# LED_board_2.net
KiCad netlist of a schematic drawn in EAGLE
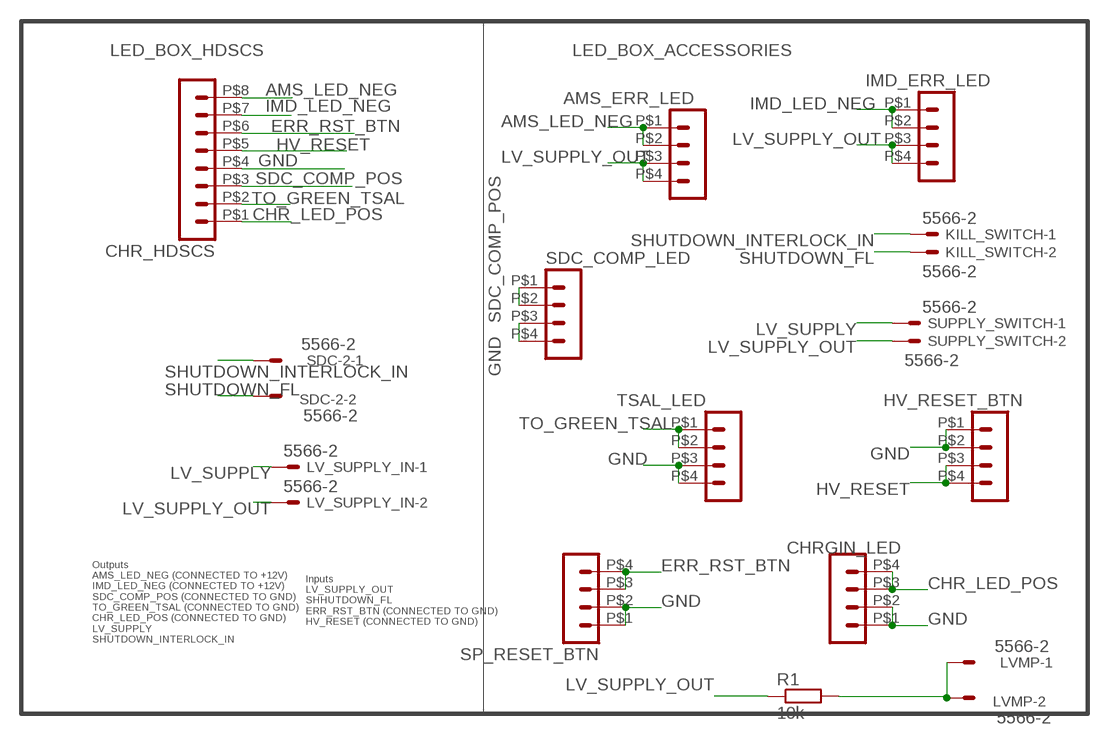
[diagram p0: schematic, sheet 1]

(export (version "E")
  (design (tool "Eeschema 10.0.6"))
  (components
    (comp (ref "AMS_ERR_LED")
      (value "HEADER_POS4_43045-0412")
      (footprint "eagle-import:43045-0412")
      (libsource (lib "eagle-import") (part "IIT_BOMBAY_Racing2 (1)_HEADER_POS4_?43045-0412"))
    )
    (comp (ref "CHRGIN_LED")
      (value "HEADER_POS4_43045-0412")
      (footprint "eagle-import:43045-0412")
      (libsource (lib "eagle-import") (part "IIT_BOMBAY_Racing2 (1)_HEADER_POS4_?43045-0412"))
    )
    (comp (ref "CHR_HDSCS")
      (value "HEADER_POS8_44914-0801")
      (footprint "eagle-import:44914-0801")
      (libsource (lib "eagle-import") (part "HEADER_POS8_?44914-0801"))
    )
    (comp (ref "HV_RESET_BTN")
      (value "HEADER_POS4_43045-0412")
      (footprint "eagle-import:43045-0412")
      (libsource (lib "eagle-import") (part "IIT_BOMBAY_Racing2 (1)_HEADER_POS4_?43045-0412"))
    )
    (comp (ref "IMD_ERR_LED")
      (value "HEADER_POS4_43045-0412")
      (footprint "eagle-import:43045-0412")
      (libsource (lib "eagle-import") (part "IIT_BOMBAY_Racing2 (1)_HEADER_POS4_?43045-0412"))
    )
    (comp (ref "KILL_SWITCH")
      (value "5566-2")
      (footprint "eagle-import:5566-2")
      (fields (field (name "MF") "MOLEX"))
      (libsource (lib "eagle-import") (part "5566-2"))
    )
    (comp (ref "LVMP")
      (value "5566-2")
      (footprint "eagle-import:5566-2")
      (fields (field (name "MF") "MOLEX"))
      (libsource (lib "eagle-import") (part "5566-2"))
    )
    (comp (ref "LV_SUPPLY_IN")
      (value "5566-2")
      (footprint "eagle-import:5566-2")
      (fields (field (name "MF") "MOLEX"))
      (libsource (lib "eagle-import") (part "5566-2"))
    )
    (comp (ref "R1")
      (value "10k")
      (footprint "eagle-import:M0805")
      (libsource (lib "eagle-import") (part "R-EU_M0805"))
    )
    (comp (ref "SDC-2")
      (value "5566-2")
      (footprint "eagle-import:5566-2")
      (fields (field (name "MF") "MOLEX"))
      (libsource (lib "eagle-import") (part "5566-2"))
    )
    (comp (ref "SDC_COMP_LED")
      (value "HEADER_POS4_44914-0401")
      (footprint "eagle-import:44914-0401")
      (libsource (lib "eagle-import") (part "HEADER_POS4_?44914-0401"))
    )
    (comp (ref "SP_RESET_BTN")
      (value "HEADER_POS4_43045-0412")
      (footprint "eagle-import:43045-0412")
      (libsource (lib "eagle-import") (part "IIT_BOMBAY_Racing2 (1)_HEADER_POS4_?43045-0412"))
    )
    (comp (ref "SUPPLY_SWITCH")
      (value "5566-2")
      (footprint "eagle-import:5566-2")
      (fields (field (name "MF") "MOLEX"))
      (libsource (lib "eagle-import") (part "5566-2"))
    )
    (comp (ref "TSAL_LED")
      (value "HEADER_POS4_43045-0412")
      (footprint "eagle-import:43045-0412")
      (libsource (lib "eagle-import") (part "IIT_BOMBAY_Racing2 (1)_HEADER_POS4_?43045-0412"))
    )
  )
  (nets
    (net (code "1") (name "/AMS_LED_NEG") (class "Default")
      (node (ref "AMS_ERR_LED") (pin "P$1") (pinfunction "1_P$1") (pintype "passive"))
      (node (ref "AMS_ERR_LED") (pin "P$2") (pinfunction "2_P$2") (pintype "passive"))
      (node (ref "CHR_HDSCS") (pin "P$8") (pinfunction "8_P$8") (pintype "passive"))
    )
    (net (code "2") (name "/CHR_LED_POS") (class "Default")
      (node (ref "CHRGIN_LED") (pin "P$3") (pinfunction "3_P$3") (pintype "passive"))
      (node (ref "CHRGIN_LED") (pin "P$4") (pinfunction "4_P$4") (pintype "passive"))
      (node (ref "CHR_HDSCS") (pin "P$1") (pinfunction "1_P$1") (pintype "passive"))
    )
    (net (code "3") (name "/ERR_RST_BTN") (class "Default")
      (node (ref "CHR_HDSCS") (pin "P$6") (pinfunction "6_P$6") (pintype "passive"))
      (node (ref "SP_RESET_BTN") (pin "P$3") (pinfunction "3_P$3") (pintype "passive"))
      (node (ref "SP_RESET_BTN") (pin "P$4") (pinfunction "4_P$4") (pintype "passive"))
    )
    (net (code "4") (name "/GND") (class "Default")
      (node (ref "CHRGIN_LED") (pin "P$1") (pinfunction "1_P$1") (pintype "passive"))
      (node (ref "CHRGIN_LED") (pin "P$2") (pinfunction "2_P$2") (pintype "passive"))
      (node (ref "CHR_HDSCS") (pin "P$4") (pinfunction "4_P$4") (pintype "passive"))
      (node (ref "HV_RESET_BTN") (pin "P$1") (pinfunction "1_P$1") (pintype "passive"))
      (node (ref "HV_RESET_BTN") (pin "P$2") (pinfunction "2_P$2") (pintype "passive"))
      (node (ref "SDC_COMP_LED") (pin "P$3") (pinfunction "3_P$3") (pintype "passive"))
      (node (ref "SDC_COMP_LED") (pin "P$4") (pinfunction "4_P$4") (pintype "passive"))
      (node (ref "SP_RESET_BTN") (pin "P$1") (pinfunction "1_P$1") (pintype "passive"))
      (node (ref "SP_RESET_BTN") (pin "P$2") (pinfunction "2_P$2") (pintype "passive"))
      (node (ref "TSAL_LED") (pin "P$3") (pinfunction "3_P$3") (pintype "passive"))
      (node (ref "TSAL_LED") (pin "P$4") (pinfunction "4_P$4") (pintype "passive"))
    )
    (net (code "5") (name "/HV_RESET") (class "Default")
      (node (ref "CHR_HDSCS") (pin "P$5") (pinfunction "5_P$5") (pintype "passive"))
      (node (ref "HV_RESET_BTN") (pin "P$3") (pinfunction "3_P$3") (pintype "passive"))
      (node (ref "HV_RESET_BTN") (pin "P$4") (pinfunction "4_P$4") (pintype "passive"))
    )
    (net (code "6") (name "/IMD_LED_NEG") (class "Default")
      (node (ref "CHR_HDSCS") (pin "P$7") (pinfunction "7_P$7") (pintype "passive"))
      (node (ref "IMD_ERR_LED") (pin "P$1") (pinfunction "1_P$1") (pintype "passive"))
      (node (ref "IMD_ERR_LED") (pin "P$2") (pinfunction "2_P$2") (pintype "passive"))
    )
    (net (code "7") (name "/LV_SUPPLY") (class "Default")
      (node (ref "LV_SUPPLY_IN") (pin "1") (pinfunction "S_1") (pintype "passive"))
      (node (ref "SUPPLY_SWITCH") (pin "1") (pinfunction "S_1") (pintype "passive"))
    )
    (net (code "8") (name "/LV_SUPPLY_OUT") (class "Default")
      (node (ref "AMS_ERR_LED") (pin "P$3") (pinfunction "3_P$3") (pintype "passive"))
      (node (ref "AMS_ERR_LED") (pin "P$4") (pinfunction "4_P$4") (pintype "passive"))
      (node (ref "IMD_ERR_LED") (pin "P$3") (pinfunction "3_P$3") (pintype "passive"))
      (node (ref "IMD_ERR_LED") (pin "P$4") (pinfunction "4_P$4") (pintype "passive"))
      (node (ref "LV_SUPPLY_IN") (pin "2") (pinfunction "S_2") (pintype "passive"))
      (node (ref "R1") (pin "1") (pinfunction "1_1") (pintype "passive"))
      (node (ref "SUPPLY_SWITCH") (pin "2") (pinfunction "S_2") (pintype "passive"))
    )
    (net (code "9") (name "/SDC_COMP_POS") (class "Default")
      (node (ref "CHR_HDSCS") (pin "P$3") (pinfunction "3_P$3") (pintype "passive"))
      (node (ref "SDC_COMP_LED") (pin "P$1") (pinfunction "1_P$1") (pintype "passive"))
      (node (ref "SDC_COMP_LED") (pin "P$2") (pinfunction "2_P$2") (pintype "passive"))
    )
    (net (code "10") (name "/SHUTDOWN_FL") (class "Default")
      (node (ref "KILL_SWITCH") (pin "2") (pinfunction "S_2") (pintype "passive"))
      (node (ref "SDC-2") (pin "2") (pinfunction "S_2") (pintype "passive"))
    )
    (net (code "11") (name "/SHUTDOWN_INTERLOCK_IN") (class "Default")
      (node (ref "KILL_SWITCH") (pin "1") (pinfunction "S_1") (pintype "passive"))
      (node (ref "SDC-2") (pin "1") (pinfunction "S_1") (pintype "passive"))
    )
    (net (code "12") (name "/TO_GREEN_TSAL") (class "Default")
      (node (ref "CHR_HDSCS") (pin "P$2") (pinfunction "2_P$2") (pintype "passive"))
      (node (ref "TSAL_LED") (pin "P$1") (pinfunction "1_P$1") (pintype "passive"))
      (node (ref "TSAL_LED") (pin "P$2") (pinfunction "2_P$2") (pintype "passive"))
    )
    (net (code "13") (name "Net-(LVMPA-S)") (class "Default")
      (node (ref "LVMP") (pin "1") (pinfunction "S_1") (pintype "passive"))
      (node (ref "LVMP") (pin "2") (pinfunction "S_2") (pintype "passive"))
      (node (ref "R1") (pin "2") (pinfunction "2_2") (pintype "passive"))
    )
  )
)
